# sch.net
KiCad netlist of a schematic drawn in EasyEDA
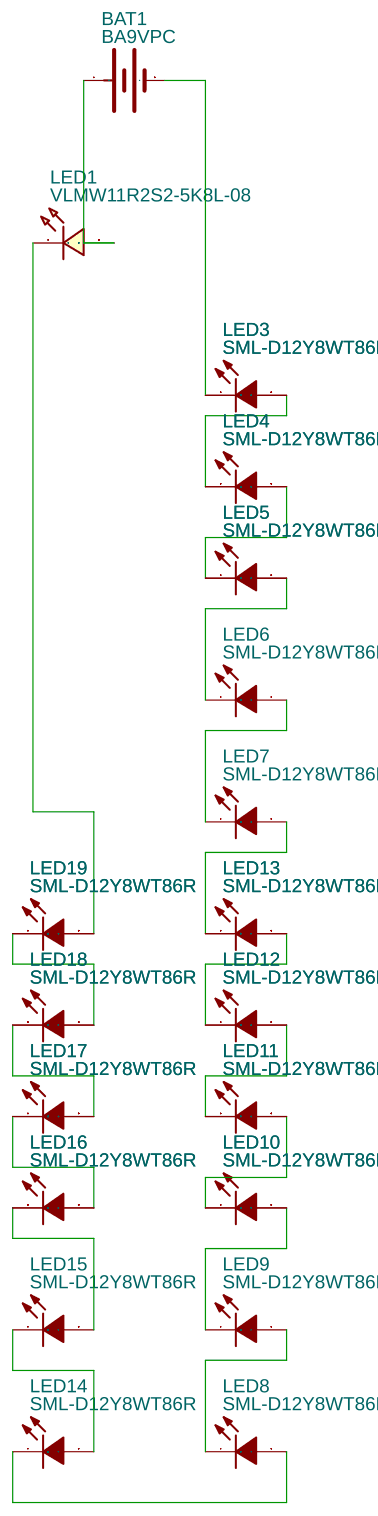
[diagram p0: schematic sheet]

(export (version "E")
  (design (tool "Eeschema 10.0.6"))
  (components
    (comp (ref "BAT1")
      (value "BA9VPC")
      (fields (field (name "Manufacturer") "MPD(Memory Protection Devices)"))
      (libsource (lib "") (part "BA9VPC"))
    )
    (comp (ref "LED1")
      (value "VLMW11R2S2-5K8L-08")
      (fields (field (name "Manufacturer") "VISHAY(威世)"))
      (libsource (lib "") (part "VLMW11R2S2-5K8L-08"))
    )
    (comp (ref "LED3")
      (value "SML-D12Y8WT86R")
      (fields (field (name "Manufacturer") "ROHM(罗姆)"))
      (libsource (lib "") (part "SML-D12Y8WT86R"))
    )
    (comp (ref "LED4")
      (value "SML-D12Y8WT86R")
      (fields (field (name "Manufacturer") "ROHM(罗姆)"))
      (libsource (lib "") (part "SML-D12Y8WT86R"))
    )
    (comp (ref "LED5")
      (value "SML-D12Y8WT86R")
      (fields (field (name "Manufacturer") "ROHM(罗姆)"))
      (libsource (lib "") (part "SML-D12Y8WT86R"))
    )
    (comp (ref "LED6")
      (value "SML-D12Y8WT86R")
      (fields (field (name "Manufacturer") "ROHM(罗姆)"))
      (libsource (lib "") (part "SML-D12Y8WT86R"))
    )
    (comp (ref "LED7")
      (value "SML-D12Y8WT86R")
      (fields (field (name "Manufacturer") "ROHM(罗姆)"))
      (libsource (lib "") (part "SML-D12Y8WT86R"))
    )
    (comp (ref "LED8")
      (value "SML-D12Y8WT86R")
      (fields (field (name "Manufacturer") "ROHM(罗姆)"))
      (libsource (lib "") (part "SML-D12Y8WT86R"))
    )
    (comp (ref "LED9")
      (value "SML-D12Y8WT86R")
      (fields (field (name "Manufacturer") "ROHM(罗姆)"))
      (libsource (lib "") (part "SML-D12Y8WT86R"))
    )
    (comp (ref "LED10")
      (value "SML-D12Y8WT86R")
      (fields (field (name "Manufacturer") "ROHM(罗姆)"))
      (libsource (lib "") (part "SML-D12Y8WT86R"))
    )
    (comp (ref "LED11")
      (value "SML-D12Y8WT86R")
      (fields (field (name "Manufacturer") "ROHM(罗姆)"))
      (libsource (lib "") (part "SML-D12Y8WT86R"))
    )
    (comp (ref "LED12")
      (value "SML-D12Y8WT86R")
      (fields (field (name "Manufacturer") "ROHM(罗姆)"))
      (libsource (lib "") (part "SML-D12Y8WT86R"))
    )
    (comp (ref "LED13")
      (value "SML-D12Y8WT86R")
      (fields (field (name "Manufacturer") "ROHM(罗姆)"))
      (libsource (lib "") (part "SML-D12Y8WT86R"))
    )
    (comp (ref "LED14")
      (value "SML-D12Y8WT86R")
      (fields (field (name "Manufacturer") "ROHM(罗姆)"))
      (libsource (lib "") (part "SML-D12Y8WT86R"))
    )
    (comp (ref "LED15")
      (value "SML-D12Y8WT86R")
      (fields (field (name "Manufacturer") "ROHM(罗姆)"))
      (libsource (lib "") (part "SML-D12Y8WT86R"))
    )
    (comp (ref "LED16")
      (value "SML-D12Y8WT86R")
      (fields (field (name "Manufacturer") "ROHM(罗姆)"))
      (libsource (lib "") (part "SML-D12Y8WT86R"))
    )
    (comp (ref "LED17")
      (value "SML-D12Y8WT86R")
      (fields (field (name "Manufacturer") "ROHM(罗姆)"))
      (libsource (lib "") (part "SML-D12Y8WT86R"))
    )
    (comp (ref "LED18")
      (value "SML-D12Y8WT86R")
      (fields (field (name "Manufacturer") "ROHM(罗姆)"))
      (libsource (lib "") (part "SML-D12Y8WT86R"))
    )
    (comp (ref "LED19")
      (value "SML-D12Y8WT86R")
      (fields (field (name "Manufacturer") "ROHM(罗姆)"))
      (libsource (lib "") (part "SML-D12Y8WT86R"))
    )
  )
  (nets
    (net (code "1") (name "Net-(BAT1-+)") (class "Default")
      (node (ref "BAT1") (pin "1") (pinfunction "+_1") (pintype "passive"))
      (node (ref "LED1") (pin "2") (pinfunction "2_2") (pintype "unspecified"))
    )
    (net (code "2") (name "Net-(BAT1--)") (class "Default")
      (node (ref "BAT1") (pin "2") (pinfunction "-_2") (pintype "passive"))
      (node (ref "LED3") (pin "1") (pinfunction "C_1") (pintype "unspecified"))
    )
    (net (code "3") (name "Net-(LED3-A)") (class "Default")
      (node (ref "LED3") (pin "2") (pinfunction "A_2") (pintype "unspecified"))
      (node (ref "LED4") (pin "1") (pinfunction "C_1") (pintype "unspecified"))
    )
    (net (code "4") (name "Net-(LED4-A)") (class "Default")
      (node (ref "LED4") (pin "2") (pinfunction "A_2") (pintype "unspecified"))
      (node (ref "LED5") (pin "1") (pinfunction "C_1") (pintype "unspecified"))
    )
    (net (code "5") (name "Net-(LED5-A)") (class "Default")
      (node (ref "LED5") (pin "2") (pinfunction "A_2") (pintype "unspecified"))
      (node (ref "LED6") (pin "1") (pinfunction "C_1") (pintype "unspecified"))
    )
    (net (code "6") (name "Net-(LED6-A)") (class "Default")
      (node (ref "LED6") (pin "2") (pinfunction "A_2") (pintype "unspecified"))
      (node (ref "LED7") (pin "1") (pinfunction "C_1") (pintype "unspecified"))
    )
    (net (code "7") (name "Net-(LED8-C)") (class "Default")
      (node (ref "LED8") (pin "1") (pinfunction "C_1") (pintype "unspecified"))
      (node (ref "LED9") (pin "2") (pinfunction "A_2") (pintype "unspecified"))
    )
    (net (code "8") (name "Net-(LED10-A)") (class "Default")
      (node (ref "LED10") (pin "2") (pinfunction "A_2") (pintype "unspecified"))
      (node (ref "LED9") (pin "1") (pinfunction "C_1") (pintype "unspecified"))
    )
    (net (code "9") (name "Net-(LED10-C)") (class "Default")
      (node (ref "LED10") (pin "1") (pinfunction "C_1") (pintype "unspecified"))
      (node (ref "LED11") (pin "2") (pinfunction "A_2") (pintype "unspecified"))
    )
    (net (code "10") (name "Net-(LED11-C)") (class "Default")
      (node (ref "LED11") (pin "1") (pinfunction "C_1") (pintype "unspecified"))
      (node (ref "LED12") (pin "2") (pinfunction "A_2") (pintype "unspecified"))
    )
    (net (code "11") (name "Net-(LED12-C)") (class "Default")
      (node (ref "LED12") (pin "1") (pinfunction "C_1") (pintype "unspecified"))
      (node (ref "LED13") (pin "2") (pinfunction "A_2") (pintype "unspecified"))
    )
    (net (code "12") (name "Net-(LED13-C)") (class "Default")
      (node (ref "LED13") (pin "1") (pinfunction "C_1") (pintype "unspecified"))
      (node (ref "LED7") (pin "2") (pinfunction "A_2") (pintype "unspecified"))
    )
    (net (code "13") (name "Net-(LED14-A)") (class "Default")
      (node (ref "LED14") (pin "2") (pinfunction "A_2") (pintype "unspecified"))
      (node (ref "LED15") (pin "1") (pinfunction "C_1") (pintype "unspecified"))
    )
    (net (code "14") (name "Net-(LED14-C)") (class "Default")
      (node (ref "LED14") (pin "1") (pinfunction "C_1") (pintype "unspecified"))
      (node (ref "LED8") (pin "2") (pinfunction "A_2") (pintype "unspecified"))
    )
    (net (code "15") (name "Net-(LED15-A)") (class "Default")
      (node (ref "LED15") (pin "2") (pinfunction "A_2") (pintype "unspecified"))
      (node (ref "LED16") (pin "1") (pinfunction "C_1") (pintype "unspecified"))
    )
    (net (code "16") (name "Net-(LED16-A)") (class "Default")
      (node (ref "LED16") (pin "2") (pinfunction "A_2") (pintype "unspecified"))
      (node (ref "LED17") (pin "1") (pinfunction "C_1") (pintype "unspecified"))
    )
    (net (code "17") (name "Net-(LED17-A)") (class "Default")
      (node (ref "LED17") (pin "2") (pinfunction "A_2") (pintype "unspecified"))
      (node (ref "LED18") (pin "1") (pinfunction "C_1") (pintype "unspecified"))
    )
    (net (code "18") (name "Net-(LED18-A)") (class "Default")
      (node (ref "LED18") (pin "2") (pinfunction "A_2") (pintype "unspecified"))
      (node (ref "LED19") (pin "1") (pinfunction "C_1") (pintype "unspecified"))
    )
    (net (code "19") (name "Net-(LED19-A)") (class "Default")
      (node (ref "LED1") (pin "1") (pinfunction "1_1") (pintype "unspecified"))
      (node (ref "LED19") (pin "2") (pinfunction "A_2") (pintype "unspecified"))
    )
  )
)
